# Sheet2.net
KiCad netlist of a schematic drawn in Altium Designer
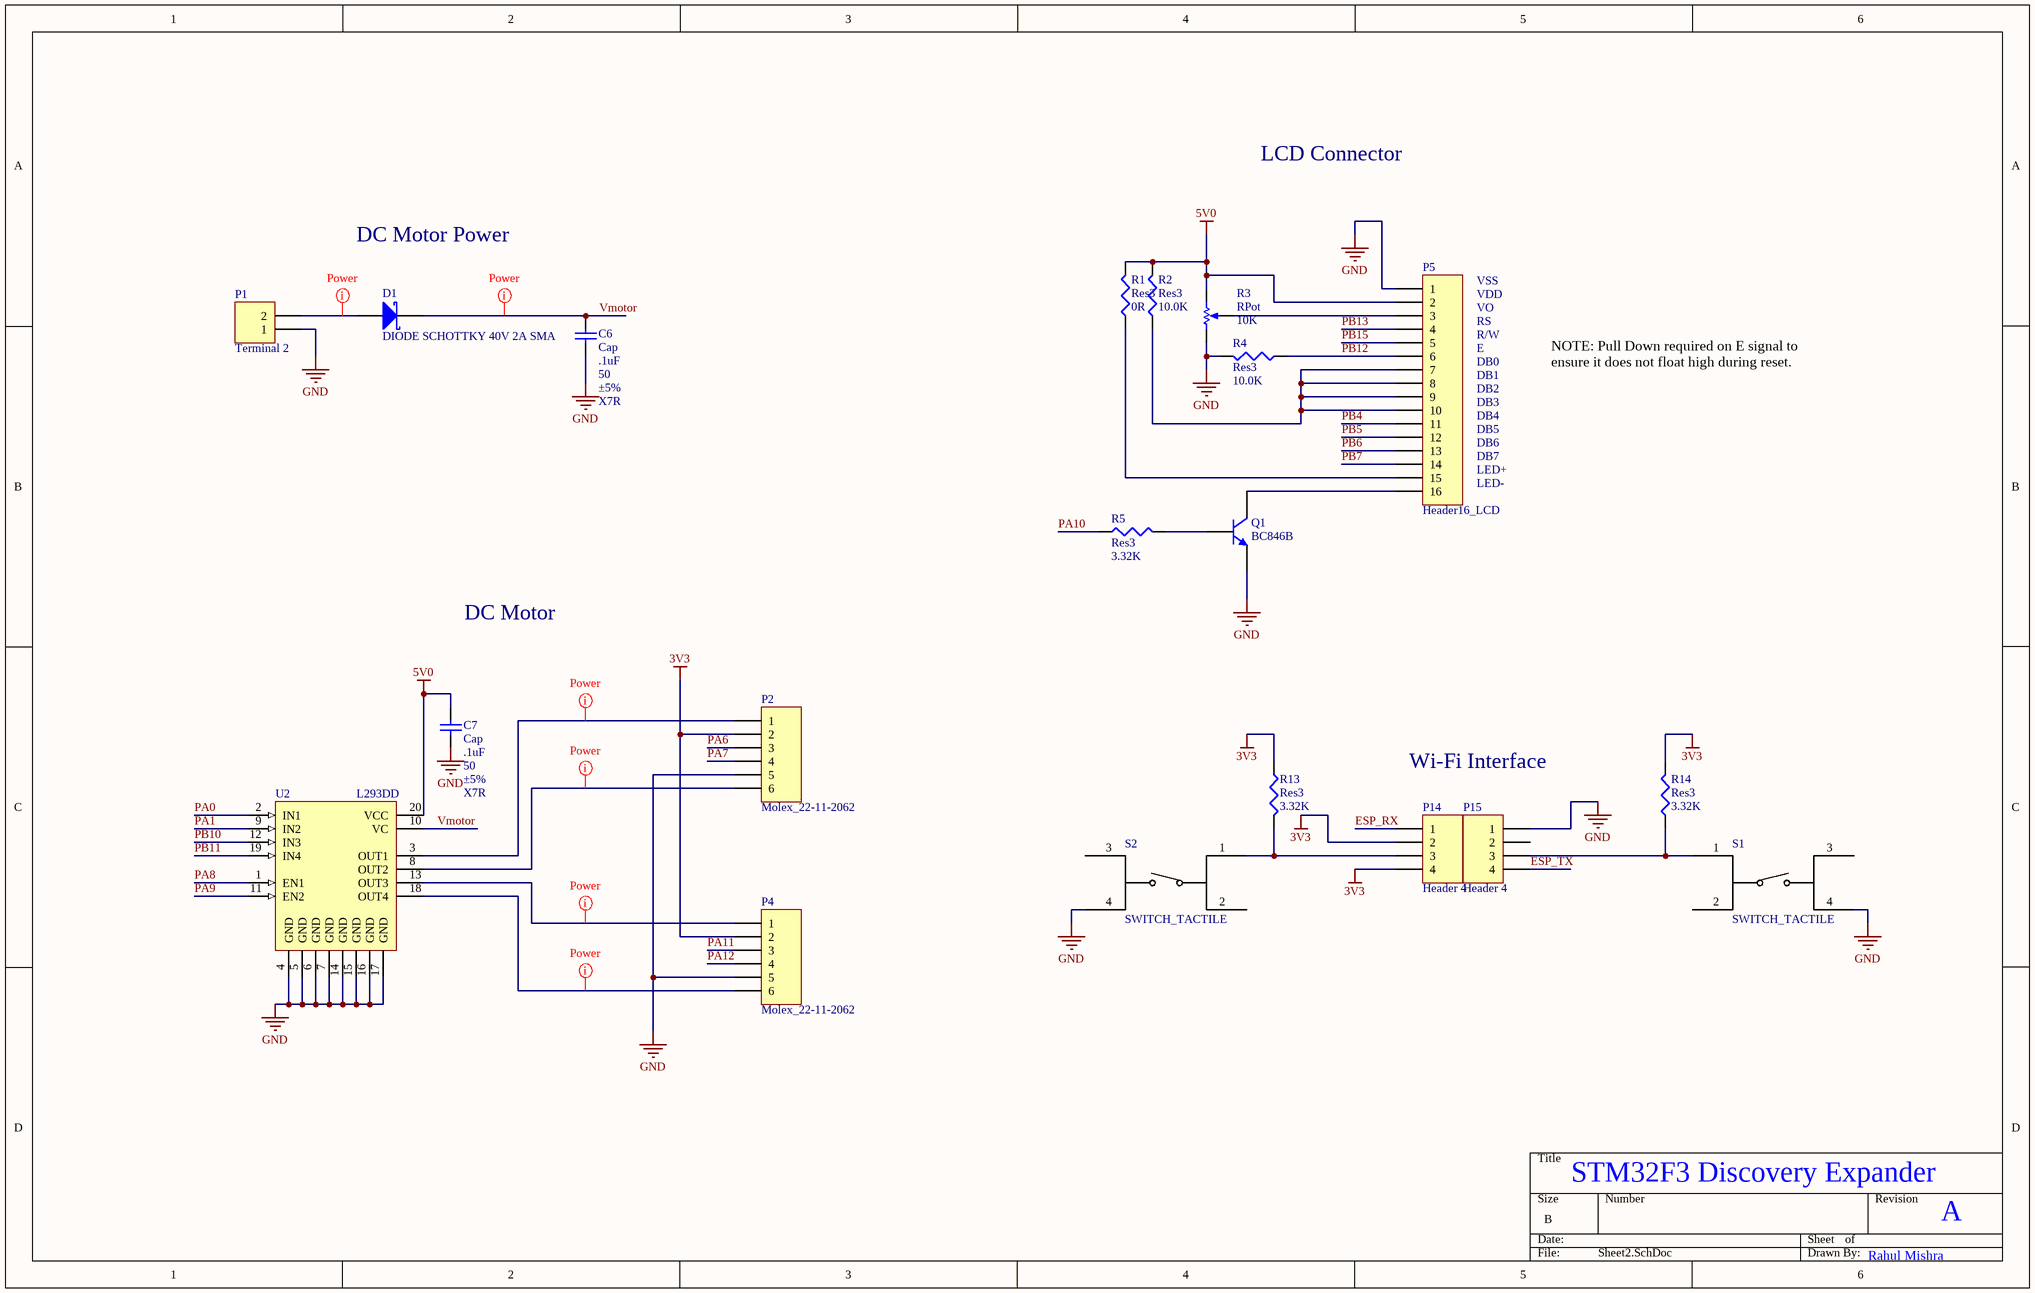
[diagram p0: Sheet2.SchDoc]

(export (version "E")
  (design (tool "Eeschema 10.0.6"))
  (components
    (comp (ref "C6")
      (value "Cap")
      (footprint "CAPC2012X09M")
      (description "CAP CER .1uF 50v X7R 0805")
      (fields
        (field (name "ALTIUM_VALUE") ".1uF")
        (field (name "WV") "50")
        (field (name "TOLERANCE") "±5%")
        (field (name "TYPE") "X7R")
        (field (name "MPN") "C0805C104J5RACTU")
      )
      (libsource (lib "esd_library") (part "CAP-X7R-.1uF-50V-±5%"))
    )
    (comp (ref "C7")
      (value "Cap")
      (footprint "CAPC2012X09M")
      (description "CAP CER .1uF 50v X7R 0805")
      (fields
        (field (name "ALTIUM_VALUE") ".1uF")
        (field (name "WV") "50")
        (field (name "TOLERANCE") "±5%")
        (field (name "TYPE") "X7R")
        (field (name "MPN") "C0805C104J5RACTU")
      )
      (libsource (lib "esd_library") (part "CAP-X7R-.1uF-50V-±5%"))
    )
    (comp (ref "D1")
      (value "DIODE SCHOTTKY 40V 2A SMA")
      (footprint "DIOM4326X23M")
      (description "Schottky Rectifier")
      (fields (field (name "MPN") "B240A-13-F"))
      (libsource (lib "esd_library") (part "DIODE SCHOTTKY 40V 2A SMA"))
    )
    (comp (ref "P1")
      (value "Terminal 2")
      (footprint "TYCO_282841_2")
      (description "Terminal, 2-Pin")
      (fields (field (name "MPN") "282841-2") (field (name "PUBLISHER") "Altium Limited"))
      (libsource (lib "esd_library") (part "Terminal 2"))
    )
    (comp (ref "P2")
      (value "Molex_22-11-2062")
      (footprint "MOLEX_22-11-2062")
      (description "CONN HEADER 6POS .100 VERT GOLD")
      (fields (field (name "MPN") "0022112062"))
      (libsource (lib "esd_library") (part "Molex_22-11-2062"))
    )
    (comp (ref "P4")
      (value "Molex_22-11-2062")
      (footprint "MOLEX_22-11-2062")
      (description "CONN HEADER 6POS .100 VERT GOLD")
      (fields (field (name "MPN") "0022112062"))
      (libsource (lib "esd_library") (part "Molex_22-11-2062"))
    )
    (comp (ref "P5")
      (value "Header16_LCD")
      (footprint "HDR1X16_LCD")
      (description "Header, 16-Pin Female")
      (fields (field (name "MPN") "PPPC161LFBN-RC"))
      (libsource (lib "esd_library") (part "Header16_LCD"))
    )
    (comp (ref "P14")
      (value "Header 4")
      (footprint "HDR1X4")
      (description "Header, 4-Pin Male")
      (fields (field (name "MPN") "PEC04SFAN"))
      (libsource (lib "esd_library") (part "Header 4"))
    )
    (comp (ref "P15")
      (value "Header 4")
      (footprint "HDR1X4")
      (description "Header, 4-Pin Male")
      (fields (field (name "MPN") "PEC04SFAN"))
      (libsource (lib "") (part "Header 4_1"))
    )
    (comp (ref "Q1")
      (value "BC846B")
      (footprint "SOT95P230X110-3M")
      (description "TRANS NPN 65V 0.1A SOT23")
      (fields (field (name "MPN") "BC846BLT3G"))
      (libsource (lib "esd_library") (part "BC846B"))
    )
    (comp (ref "R1")
      (value "Res3")
      (footprint "RESC2112X05M")
      (description "RES SMD 0 OHM 5% 1/8W 0805")
      (fields (field (name "MPN") "CRCW08050000Z0EA") (field (name "ALTIUM_VALUE") "0R"))
      (libsource (lib "esd_library") (part "Resistor_0R_Jumper"))
    )
    (comp (ref "R2")
      (value "Res3")
      (footprint "RESC2112X05M")
      (description "RES SMD 10.0K OHM 1% 1/8W 0805")
      (fields (field (name "ALTIUM_VALUE") "10.0K") (field (name "MPN") "CRCW080510K0FKEA"))
      (libsource (lib "esd_library") (part "Resistor_10.0K"))
    )
    (comp (ref "R3")
      (value "RPot")
      (footprint "BOURNS_3386F")
      (description "POT 10K OHM THUMBWHEEL CERM ST")
      (fields
        (field (name "MPN") "3352T-1-103LF")
        (field (name "ALTIUM_VALUE") "10K")
        (field (name "PUBLISHER") "Altium Limited")
      )
      (libsource (lib "esd_library") (part "RPot"))
    )
    (comp (ref "R4")
      (value "Res3")
      (footprint "RESC2112X05M")
      (description "RES SMD 10.0K OHM 1% 1/8W 0805")
      (fields (field (name "ALTIUM_VALUE") "10.0K") (field (name "MPN") "CRCW080510K0FKEA"))
      (libsource (lib "esd_library") (part "Resistor_10.0K"))
    )
    (comp (ref "R5")
      (value "Res3")
      (footprint "RESC2112X05M")
      (description "RES SMD 3.32K OHM 1% 1/8W 0805")
      (fields (field (name "ALTIUM_VALUE") "3.32K") (field (name "MPN") "CRCW08053K32FKEA"))
      (libsource (lib "esd_library") (part "Resistor_3.32K"))
    )
    (comp (ref "R13")
      (value "Res3")
      (footprint "RESC2112X05M")
      (description "RES SMD 3.32K OHM 1% 1/8W 0805")
      (fields (field (name "ALTIUM_VALUE") "3.32K") (field (name "MPN") "CRCW08053K32FKEA"))
      (libsource (lib "esd_library") (part "Resistor_3.32K"))
    )
    (comp (ref "R14")
      (value "Res3")
      (footprint "RESC2112X05M")
      (description "RES SMD 3.32K OHM 1% 1/8W 0805")
      (fields (field (name "ALTIUM_VALUE") "3.32K") (field (name "MPN") "CRCW08053K32FKEA"))
      (libsource (lib "esd_library") (part "Resistor_3.32K"))
    )
    (comp (ref "S1")
      (value "SWITCH_TACTILE")
      (footprint "TACT_SWITCH_6MM_SMT")
      (description "SWITCH TACTILE SPST-NO 0.05A 12V")
      (fields (field (name "MPN") "PTS645SH50SMTR92 LFS"))
      (libsource (lib "esd_library") (part "SWITCH_TACTILE"))
    )
    (comp (ref "S2")
      (value "SWITCH_TACTILE")
      (footprint "TACT_SWITCH_6MM_SMT")
      (description "SWITCH TACTILE SPST-NO 0.05A 12V")
      (fields (field (name "MPN") "PTS645SH50SMTR92 LFS"))
      (libsource (lib "esd_library") (part "SWITCH_TACTILE"))
    )
    (comp (ref "U2")
      (value "L293DD")
      (footprint "SO20_N")
      (description "IC MOTOR DRIVER PAR 20-SOIC")
      (fields (field (name "MPN") "L293DD013TR") (field (name "PUBLISHER") "Altium Limited"))
      (libsource (lib "esd_library") (part "L293DD"))
    )
  )
  (nets
    (net (code "1") (name "/ESP_RX") (class "Default")
      (node (ref "P14") (pin "1") (pinfunction "1_1") (pintype "passive"))
    )
    (net (code "2") (name "/ESP_TX") (class "Default")
      (node (ref "P15") (pin "4") (pinfunction "4_4") (pintype "passive"))
    )
    (net (code "3") (name "/PA0") (class "Default")
      (node (ref "U2") (pin "2") (pinfunction "IN1_2") (pintype "input"))
    )
    (net (code "4") (name "/PA1") (class "Default")
      (node (ref "U2") (pin "9") (pinfunction "IN2_9") (pintype "input"))
    )
    (net (code "5") (name "/PA6") (class "Default")
      (node (ref "P2") (pin "3") (pinfunction "3_3") (pintype "passive"))
    )
    (net (code "6") (name "/PA7") (class "Default")
      (node (ref "P2") (pin "4") (pinfunction "4_4") (pintype "passive"))
    )
    (net (code "7") (name "/PA8") (class "Default")
      (node (ref "U2") (pin "1") (pinfunction "EN1_1") (pintype "input"))
    )
    (net (code "8") (name "/PA9") (class "Default")
      (node (ref "U2") (pin "11") (pinfunction "EN2_11") (pintype "input"))
    )
    (net (code "9") (name "/PA10") (class "Default")
      (node (ref "R5") (pin "1") (pinfunction "1_1") (pintype "passive"))
    )
    (net (code "10") (name "/PA11") (class "Default")
      (node (ref "P4") (pin "3") (pinfunction "3_3") (pintype "passive"))
    )
    (net (code "11") (name "/PA12") (class "Default")
      (node (ref "P4") (pin "4") (pinfunction "4_4") (pintype "passive"))
    )
    (net (code "12") (name "/PB4") (class "Default")
      (node (ref "P5") (pin "11") (pinfunction "11_11") (pintype "passive"))
    )
    (net (code "13") (name "/PB5") (class "Default")
      (node (ref "P5") (pin "12") (pinfunction "12_12") (pintype "passive"))
    )
    (net (code "14") (name "/PB6") (class "Default")
      (node (ref "P5") (pin "13") (pinfunction "13_13") (pintype "passive"))
    )
    (net (code "15") (name "/PB7") (class "Default")
      (node (ref "P5") (pin "14") (pinfunction "14_14") (pintype "passive"))
    )
    (net (code "16") (name "/PB10") (class "Default")
      (node (ref "U2") (pin "12") (pinfunction "IN3_12") (pintype "input"))
    )
    (net (code "17") (name "/PB11") (class "Default")
      (node (ref "U2") (pin "19") (pinfunction "IN4_19") (pintype "input"))
    )
    (net (code "18") (name "/PB12") (class "Default")
      (node (ref "P5") (pin "6") (pinfunction "6_6") (pintype "passive"))
      (node (ref "R4") (pin "1") (pinfunction "1_1") (pintype "passive"))
    )
    (net (code "19") (name "/PB13") (class "Default")
      (node (ref "P5") (pin "4") (pinfunction "4_4") (pintype "passive"))
    )
    (net (code "20") (name "/PB15") (class "Default")
      (node (ref "P5") (pin "5") (pinfunction "5_5") (pintype "passive"))
    )
    (net (code "21") (name "/Vmotor") (class "Default")
      (node (ref "C6") (pin "2") (pinfunction "2_2") (pintype "passive"))
      (node (ref "D1") (pin "1") (pinfunction "K_1") (pintype "passive"))
      (node (ref "U2") (pin "10") (pinfunction "VC_10") (pintype "power_in"))
    )
    (net (code "22") (name "3V3") (class "Default")
      (node (ref "P14") (pin "2") (pinfunction "2_2") (pintype "passive"))
      (node (ref "P14") (pin "4") (pinfunction "4_4") (pintype "passive"))
      (node (ref "P2") (pin "2") (pinfunction "2_2") (pintype "passive"))
      (node (ref "P4") (pin "2") (pinfunction "2_2") (pintype "passive"))
      (node (ref "R13") (pin "2") (pinfunction "2_2") (pintype "passive"))
      (node (ref "R14") (pin "2") (pinfunction "2_2") (pintype "passive"))
    )
    (net (code "23") (name "5V0") (class "Default")
      (node (ref "C7") (pin "2") (pinfunction "2_2") (pintype "passive"))
      (node (ref "P5") (pin "2") (pinfunction "2_2") (pintype "passive"))
      (node (ref "R1") (pin "2") (pinfunction "2_2") (pintype "passive"))
      (node (ref "R2") (pin "2") (pinfunction "2_2") (pintype "passive"))
      (node (ref "R3") (pin "3") (pinfunction "BOT_3") (pintype "passive"))
      (node (ref "U2") (pin "20") (pinfunction "VCC_20") (pintype "power_in"))
    )
    (net (code "24") (name "GND") (class "Default")
      (node (ref "C6") (pin "1") (pinfunction "1_1") (pintype "passive"))
      (node (ref "C7") (pin "1") (pinfunction "1_1") (pintype "passive"))
      (node (ref "P1") (pin "1") (pinfunction "1_1") (pintype "passive"))
      (node (ref "P15") (pin "1") (pinfunction "1_1") (pintype "passive"))
      (node (ref "P2") (pin "5") (pinfunction "5_5") (pintype "passive"))
      (node (ref "P4") (pin "5") (pinfunction "5_5") (pintype "passive"))
      (node (ref "P5") (pin "1") (pinfunction "1_1") (pintype "passive"))
      (node (ref "Q1") (pin "2") (pinfunction "E_2") (pintype "passive"))
      (node (ref "R3") (pin "1") (pinfunction "TOP_1") (pintype "passive"))
      (node (ref "R4") (pin "2") (pinfunction "2_2") (pintype "passive"))
      (node (ref "S1") (pin "4") (pinfunction "4_4") (pintype "passive"))
      (node (ref "S2") (pin "4") (pinfunction "4_4") (pintype "passive"))
      (node (ref "U2") (pin "14") (pinfunction "GND_14") (pintype "power_in"))
      (node (ref "U2") (pin "15") (pinfunction "GND_15") (pintype "power_in"))
      (node (ref "U2") (pin "16") (pinfunction "GND_16") (pintype "power_in"))
      (node (ref "U2") (pin "17") (pinfunction "GND_17") (pintype "power_in"))
      (node (ref "U2") (pin "4") (pinfunction "GND_4") (pintype "power_in"))
      (node (ref "U2") (pin "5") (pinfunction "GND_5") (pintype "power_in"))
      (node (ref "U2") (pin "6") (pinfunction "GND_6") (pintype "power_in"))
      (node (ref "U2") (pin "7") (pinfunction "GND_7") (pintype "power_in"))
    )
    (net (code "25") (name "Net-(D1-A)") (class "Default")
      (node (ref "D1") (pin "2") (pinfunction "A_2") (pintype "passive"))
      (node (ref "P1") (pin "2") (pinfunction "2_2") (pintype "passive"))
    )
    (net (code "26") (name "Net-(P5-Pad10)") (class "Default")
      (node (ref "P5") (pin "10") (pinfunction "10_10") (pintype "passive"))
      (node (ref "P5") (pin "7") (pinfunction "7_7") (pintype "passive"))
      (node (ref "P5") (pin "8") (pinfunction "8_8") (pintype "passive"))
      (node (ref "P5") (pin "9") (pinfunction "9_9") (pintype "passive"))
      (node (ref "R2") (pin "1") (pinfunction "1_1") (pintype "passive"))
    )
    (net (code "27") (name "Net-(P5-Pad15)") (class "Default")
      (node (ref "P5") (pin "15") (pinfunction "15_15") (pintype "passive"))
      (node (ref "R1") (pin "1") (pinfunction "1_1") (pintype "passive"))
    )
    (net (code "28") (name "Net-(P14-Pad3)") (class "Default")
      (node (ref "P14") (pin "3") (pinfunction "3_3") (pintype "passive"))
      (node (ref "R13") (pin "1") (pinfunction "1_1") (pintype "passive"))
      (node (ref "S2") (pin "1") (pinfunction "1_1") (pintype "passive"))
    )
    (net (code "29") (name "Net-(P15-Pad3)") (class "Default")
      (node (ref "P15") (pin "3") (pinfunction "3_3") (pintype "passive"))
      (node (ref "R14") (pin "1") (pinfunction "1_1") (pintype "passive"))
      (node (ref "S1") (pin "1") (pinfunction "1_1") (pintype "passive"))
    )
    (net (code "30") (name "Net-(Q1-B)") (class "Default")
      (node (ref "Q1") (pin "1") (pinfunction "B_1") (pintype "passive"))
      (node (ref "R5") (pin "2") (pinfunction "2_2") (pintype "passive"))
    )
    (net (code "31") (name "Net-(Q1-C)") (class "Default")
      (node (ref "P5") (pin "16") (pinfunction "16_16") (pintype "passive"))
      (node (ref "Q1") (pin "3") (pinfunction "C_3") (pintype "passive"))
    )
    (net (code "32") (name "Net-(R3-TAP)") (class "Default")
      (node (ref "P5") (pin "3") (pinfunction "3_3") (pintype "passive"))
      (node (ref "R3") (pin "2") (pinfunction "TAP_2") (pintype "passive"))
    )
    (net (code "33") (name "Net-(U2-OUT1)") (class "Default")
      (node (ref "P2") (pin "1") (pinfunction "1_1") (pintype "passive"))
      (node (ref "U2") (pin "3") (pinfunction "OUT1_3") (pintype "tri_state"))
    )
    (net (code "34") (name "Net-(U2-OUT2)") (class "Default")
      (node (ref "P2") (pin "6") (pinfunction "6_6") (pintype "passive"))
      (node (ref "U2") (pin "8") (pinfunction "OUT2_8") (pintype "tri_state"))
    )
    (net (code "35") (name "Net-(U2-OUT3)") (class "Default")
      (node (ref "P4") (pin "1") (pinfunction "1_1") (pintype "passive"))
      (node (ref "U2") (pin "13") (pinfunction "OUT3_13") (pintype "tri_state"))
    )
    (net (code "36") (name "Net-(U2-OUT4)") (class "Default")
      (node (ref "P4") (pin "6") (pinfunction "6_6") (pintype "passive"))
      (node (ref "U2") (pin "18") (pinfunction "OUT4_18") (pintype "tri_state"))
    )
    (net (code "37") (name "unconnected-(P15-Pad2)") (class "Default")
      (node (ref "P15") (pin "2") (pinfunction "2_2") (pintype "passive"))
    )
    (net (code "38") (name "unconnected-(S1-Pad2)") (class "Default")
      (node (ref "S1") (pin "2") (pinfunction "2_2") (pintype "passive"))
    )
    (net (code "39") (name "unconnected-(S1-Pad3)") (class "Default")
      (node (ref "S1") (pin "3") (pinfunction "3_3") (pintype "passive"))
    )
    (net (code "40") (name "unconnected-(S2-Pad2)") (class "Default")
      (node (ref "S2") (pin "2") (pinfunction "2_2") (pintype "passive"))
    )
    (net (code "41") (name "unconnected-(S2-Pad3)") (class "Default")
      (node (ref "S2") (pin "3") (pinfunction "3_3") (pintype "passive"))
    )
  )
)
